# audino1012_ui.net
KiCad netlist of a schematic drawn in EAGLE
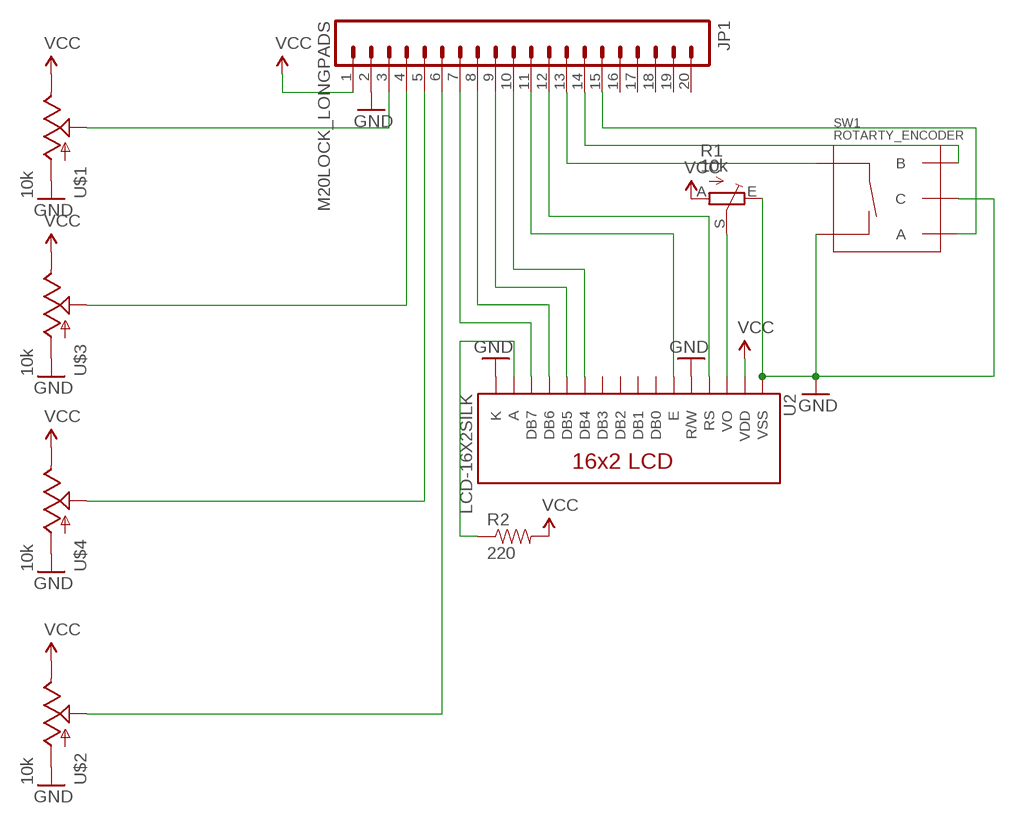
[diagram p0: schematic, sheet 1]

(export (version "E")
  (design (tool "Eeschema 10.0.6"))
  (components
    (comp (ref "JP1")
      (value "M20LOCK_LONGPADS")
      (footprint "eagle-import:1X20_LOCK_LONGPADS")
      (libsource (lib "eagle-import") (part "M20LOCK_LONGPADS"))
    )
    (comp (ref "R1")
      (value "10k")
      (footprint "eagle-import:RJ9W")
      (libsource (lib "eagle-import") (part "TRIM_EU-RJ9W"))
    )
    (comp (ref "R2")
      (value "220")
      (footprint "eagle-import:AXIAL-0.3-KIT")
      (libsource (lib "eagle-import") (part "RESISTORKIT"))
    )
    (comp (ref "SW1")
      (value "ROTARTY_ENCODER")
      (footprint "eagle-import:ROTARY_ENC_PLAIN")
      (libsource (lib "eagle-import") (part "ROTARTY_ENCODER"))
    )
    (comp (ref "U$1")
      (value "10k")
      (footprint "eagle-import:ALPS_POT")
      (libsource (lib "eagle-import") (part "POT"))
    )
    (comp (ref "U$2")
      (value "10k")
      (footprint "eagle-import:ALPS_POT")
      (libsource (lib "eagle-import") (part "POT"))
    )
    (comp (ref "U$3")
      (value "10k")
      (footprint "eagle-import:ALPS_POT")
      (libsource (lib "eagle-import") (part "POT"))
    )
    (comp (ref "U$4")
      (value "10k")
      (footprint "eagle-import:ALPS_POT")
      (libsource (lib "eagle-import") (part "POT"))
    )
    (comp (ref "U2")
      (value "LCD-16X2SILK")
      (footprint "eagle-import:LCD-16X2")
      (libsource (lib "eagle-import") (part "LCD-16X2SILK"))
    )
  )
  (nets
    (net (code "1") (name "GND") (class "Default")
      (node (ref "JP1") (pin "2") (pinfunction "2_2") (pintype "passive"))
      (node (ref "R1") (pin "E") (pinfunction "E_E") (pintype "passive"))
      (node (ref "SW1") (pin "C") (pinfunction "C_C") (pintype "bidirectional"))
      (node (ref "SW1") (pin "SW-") (pinfunction "SW-_SW-") (pintype "bidirectional"))
      (node (ref "U$1") (pin "P$3") (pinfunction "A_P$3") (pintype "passive"))
      (node (ref "U$2") (pin "P$3") (pinfunction "A_P$3") (pintype "passive"))
      (node (ref "U$3") (pin "P$3") (pinfunction "A_P$3") (pintype "passive"))
      (node (ref "U$4") (pin "P$3") (pinfunction "A_P$3") (pintype "passive"))
      (node (ref "U2") (pin "1") (pinfunction "VSS_1") (pintype "power_in"))
      (node (ref "U2") (pin "16") (pinfunction "K_16") (pintype "power_in"))
      (node (ref "U2") (pin "5") (pinfunction "R/W_5") (pintype "input"))
    )
    (net (code "2") (name "Net-(JP1-Pad13)") (class "Default")
      (node (ref "JP1") (pin "13") (pinfunction "13_13") (pintype "passive"))
      (node (ref "SW1") (pin "SW+") (pinfunction "SW+_SW+") (pintype "bidirectional"))
    )
    (net (code "3") (name "Net-(JP1-Pad14)") (class "Default")
      (node (ref "JP1") (pin "14") (pinfunction "14_14") (pintype "passive"))
      (node (ref "SW1") (pin "B") (pinfunction "B_B") (pintype "bidirectional"))
    )
    (net (code "4") (name "Net-(JP1-Pad15)") (class "Default")
      (node (ref "JP1") (pin "15") (pinfunction "15_15") (pintype "passive"))
      (node (ref "SW1") (pin "A") (pinfunction "A_A") (pintype "bidirectional"))
    )
    (net (code "5") (name "Net-(R2-1)") (class "Default")
      (node (ref "R2") (pin "P$1") (pinfunction "1_P$1") (pintype "passive"))
      (node (ref "U2") (pin "15") (pinfunction "A_15") (pintype "power_in"))
    )
    (net (code "6") (name "Net-(U$1-S)") (class "Default")
      (node (ref "JP1") (pin "3") (pinfunction "3_3") (pintype "passive"))
      (node (ref "U$1") (pin "P$2") (pinfunction "S_P$2") (pintype "passive"))
    )
    (net (code "7") (name "Net-(U$2-S)") (class "Default")
      (node (ref "JP1") (pin "6") (pinfunction "6_6") (pintype "passive"))
      (node (ref "U$2") (pin "P$2") (pinfunction "S_P$2") (pintype "passive"))
    )
    (net (code "8") (name "Net-(U$3-S)") (class "Default")
      (node (ref "JP1") (pin "4") (pinfunction "4_4") (pintype "passive"))
      (node (ref "U$3") (pin "P$2") (pinfunction "S_P$2") (pintype "passive"))
    )
    (net (code "9") (name "Net-(U$4-S)") (class "Default")
      (node (ref "JP1") (pin "5") (pinfunction "5_5") (pintype "passive"))
      (node (ref "U$4") (pin "P$2") (pinfunction "S_P$2") (pintype "passive"))
    )
    (net (code "10") (name "Net-(U2-DB4)") (class "Default")
      (node (ref "JP1") (pin "10") (pinfunction "10_10") (pintype "passive"))
      (node (ref "U2") (pin "11") (pinfunction "DB4_11") (pintype "bidirectional"))
    )
    (net (code "11") (name "Net-(U2-DB5)") (class "Default")
      (node (ref "JP1") (pin "9") (pinfunction "9_9") (pintype "passive"))
      (node (ref "U2") (pin "12") (pinfunction "DB5_12") (pintype "bidirectional"))
    )
    (net (code "12") (name "Net-(U2-DB6)") (class "Default")
      (node (ref "JP1") (pin "8") (pinfunction "8_8") (pintype "passive"))
      (node (ref "U2") (pin "13") (pinfunction "DB6_13") (pintype "bidirectional"))
    )
    (net (code "13") (name "Net-(U2-DB7)") (class "Default")
      (node (ref "JP1") (pin "7") (pinfunction "7_7") (pintype "passive"))
      (node (ref "U2") (pin "14") (pinfunction "DB7_14") (pintype "bidirectional"))
    )
    (net (code "14") (name "Net-(U2-E)") (class "Default")
      (node (ref "JP1") (pin "11") (pinfunction "11_11") (pintype "passive"))
      (node (ref "U2") (pin "6") (pinfunction "E_6") (pintype "input"))
    )
    (net (code "15") (name "Net-(U2-RS)") (class "Default")
      (node (ref "JP1") (pin "12") (pinfunction "12_12") (pintype "passive"))
      (node (ref "U2") (pin "4") (pinfunction "RS_4") (pintype "input"))
    )
    (net (code "16") (name "Net-(U2-VO)") (class "Default")
      (node (ref "R1") (pin "S") (pinfunction "S_S") (pintype "passive"))
      (node (ref "U2") (pin "3") (pinfunction "VO_3") (pintype "bidirectional"))
    )
    (net (code "17") (name "VCC") (class "Default")
      (node (ref "JP1") (pin "1") (pinfunction "1_1") (pintype "passive"))
      (node (ref "R1") (pin "A") (pinfunction "A_A") (pintype "passive"))
      (node (ref "R2") (pin "P$2") (pinfunction "2_P$2") (pintype "passive"))
      (node (ref "U$1") (pin "P$1") (pinfunction "E_P$1") (pintype "passive"))
      (node (ref "U$2") (pin "P$1") (pinfunction "E_P$1") (pintype "passive"))
      (node (ref "U$3") (pin "P$1") (pinfunction "E_P$1") (pintype "passive"))
      (node (ref "U$4") (pin "P$1") (pinfunction "E_P$1") (pintype "passive"))
      (node (ref "U2") (pin "2") (pinfunction "VDD_2") (pintype "power_in"))
    )
    (net (code "18") (name "unconnected-(JP1-Pad16)") (class "Default")
      (node (ref "JP1") (pin "16") (pinfunction "16_16") (pintype "passive"))
    )
    (net (code "19") (name "unconnected-(JP1-Pad17)") (class "Default")
      (node (ref "JP1") (pin "17") (pinfunction "17_17") (pintype "passive"))
    )
    (net (code "20") (name "unconnected-(JP1-Pad18)") (class "Default")
      (node (ref "JP1") (pin "18") (pinfunction "18_18") (pintype "passive"))
    )
    (net (code "21") (name "unconnected-(JP1-Pad19)") (class "Default")
      (node (ref "JP1") (pin "19") (pinfunction "19_19") (pintype "passive"))
    )
    (net (code "22") (name "unconnected-(JP1-Pad20)") (class "Default")
      (node (ref "JP1") (pin "20") (pinfunction "20_20") (pintype "passive"))
    )
    (net (code "23") (name "unconnected-(U2-DB0-Pad7)") (class "Default")
      (node (ref "U2") (pin "7") (pinfunction "DB0_7") (pintype "bidirectional"))
    )
    (net (code "24") (name "unconnected-(U2-DB1-Pad8)") (class "Default")
      (node (ref "U2") (pin "8") (pinfunction "DB1_8") (pintype "bidirectional"))
    )
    (net (code "25") (name "unconnected-(U2-DB2-Pad9)") (class "Default")
      (node (ref "U2") (pin "9") (pinfunction "DB2_9") (pintype "bidirectional"))
    )
    (net (code "26") (name "unconnected-(U2-DB3-Pad10)") (class "Default")
      (node (ref "U2") (pin "10") (pinfunction "DB3_10") (pintype "bidirectional"))
    )
  )
)
